# Robot_Arm_2_0.net
KiCad netlist of a schematic drawn in EAGLE
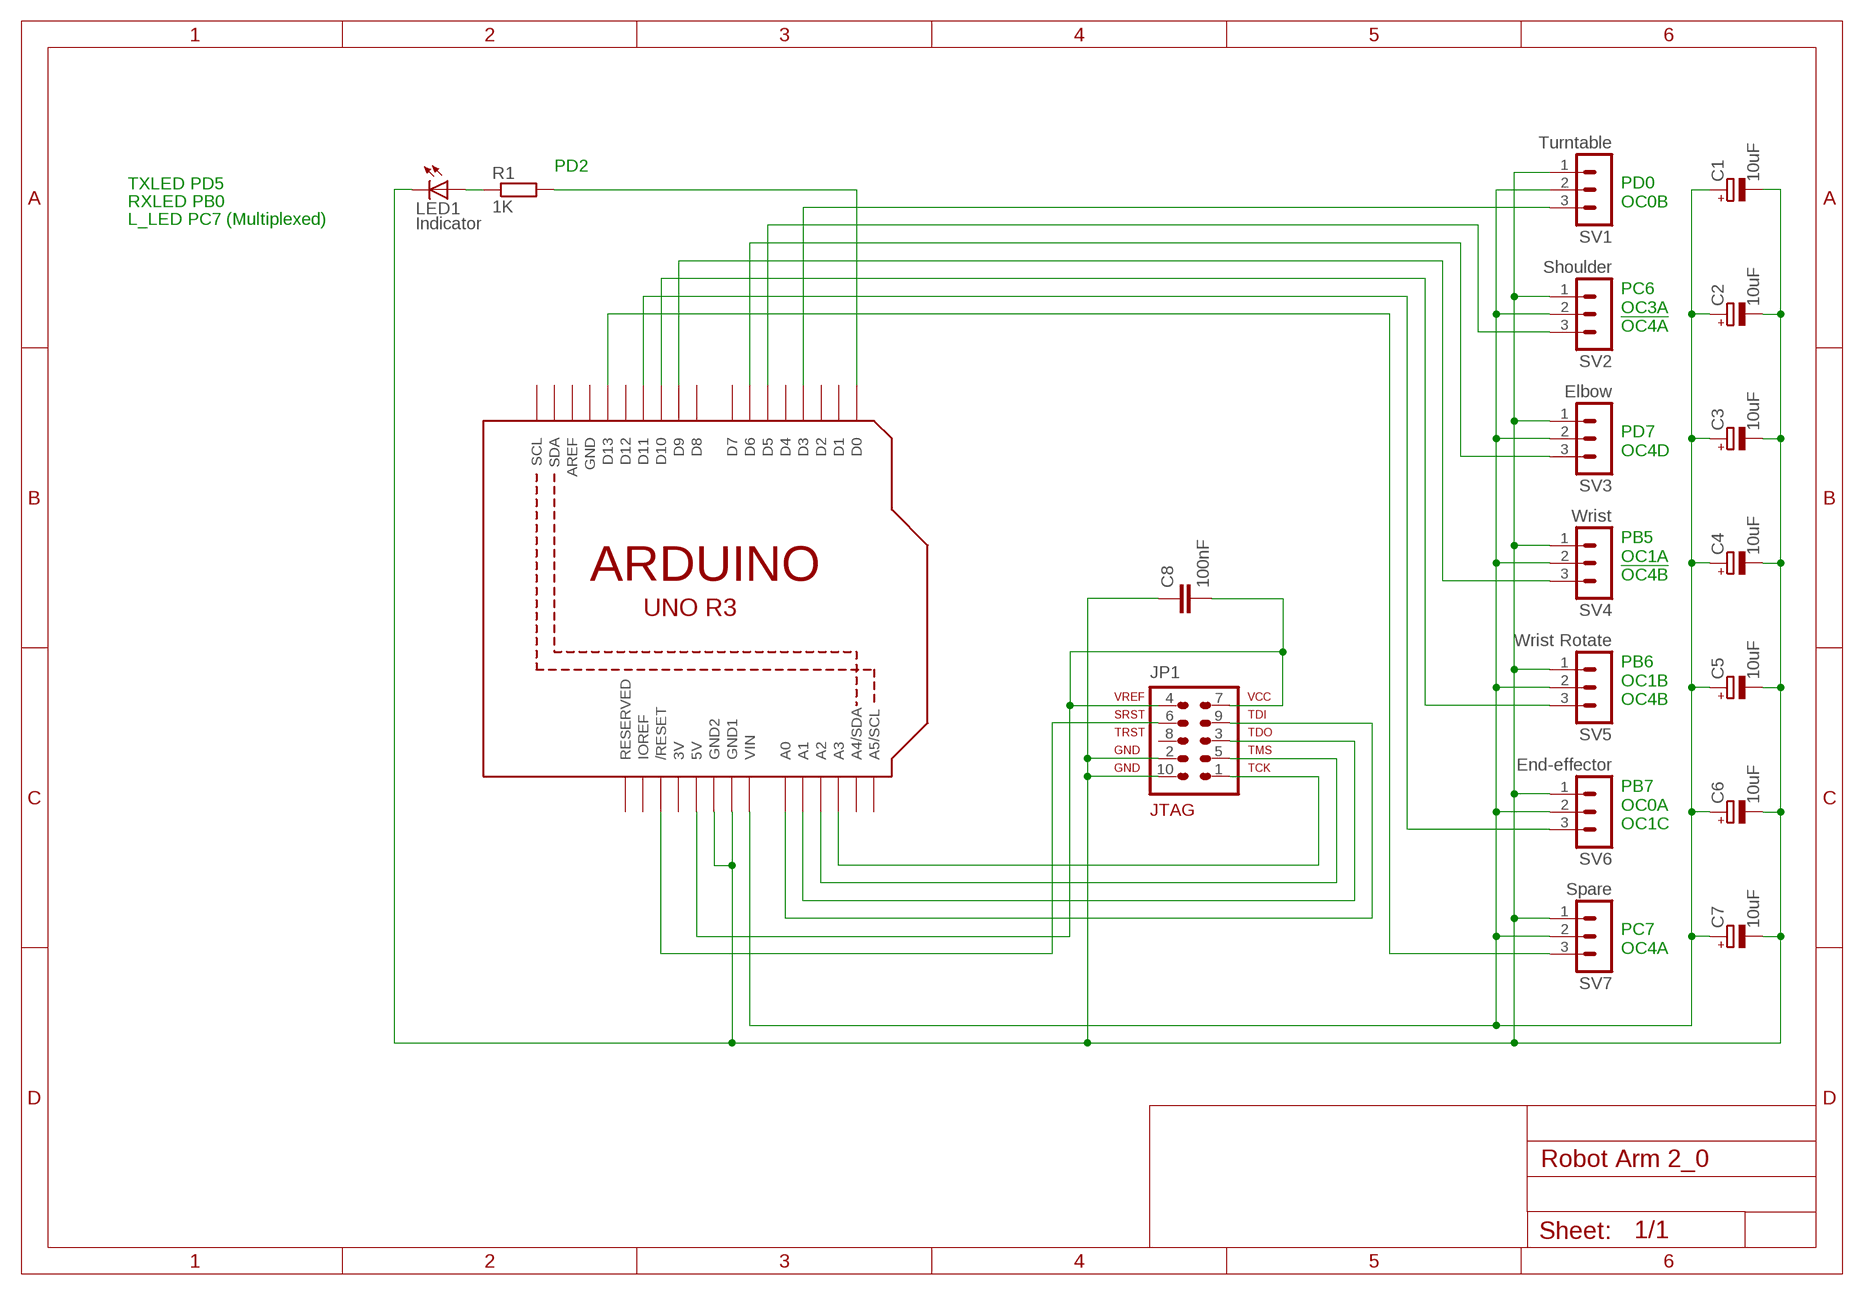
[diagram p0: schematic, sheet 1]

(export (version "E")
  (design (tool "Eeschema 10.0.6"))
  (components
    (comp (ref "C1")
      (value "10uF")
      (footprint "eagle-import:E2,5-5")
      (libsource (lib "eagle-import") (part "CPOL-EUE2.5-5"))
    )
    (comp (ref "C2")
      (value "10uF")
      (footprint "eagle-import:E2,5-5")
      (libsource (lib "eagle-import") (part "CPOL-EUE2.5-5"))
    )
    (comp (ref "C3")
      (value "10uF")
      (footprint "eagle-import:E2,5-5")
      (libsource (lib "eagle-import") (part "CPOL-EUE2.5-5"))
    )
    (comp (ref "C4")
      (value "10uF")
      (footprint "eagle-import:E2,5-5")
      (libsource (lib "eagle-import") (part "CPOL-EUE2.5-5"))
    )
    (comp (ref "C5")
      (value "10uF")
      (footprint "eagle-import:E2,5-5")
      (libsource (lib "eagle-import") (part "CPOL-EUE2.5-5"))
    )
    (comp (ref "C6")
      (value "10uF")
      (footprint "eagle-import:E2,5-5")
      (libsource (lib "eagle-import") (part "CPOL-EUE2.5-5"))
    )
    (comp (ref "C7")
      (value "10uF")
      (footprint "eagle-import:E2,5-5")
      (libsource (lib "eagle-import") (part "CPOL-EUE2.5-5"))
    )
    (comp (ref "C8")
      (value "100nF")
      (footprint "eagle-import:C075-032X103")
      (libsource (lib "eagle-import") (part "C-EU075-032X103"))
    )
    (comp (ref "JP1")
      (value "AVR-JTAG-10")
      (footprint "eagle-import:AVR-JTAG-10")
      (libsource (lib "eagle-import") (part "AVR-JTAG-10"))
    )
    (comp (ref "LED1")
      (value "Indicator")
      (footprint "eagle-import:LED3MM")
      (libsource (lib "eagle-import") (part "LED3MM"))
    )
    (comp (ref "R1")
      (value "1K")
      (footprint "eagle-import:0207_10")
      (libsource (lib "eagle-import") (part "R-EU_0207/10"))
    )
    (comp (ref "SV1")
      (value "Turntable")
      (footprint "eagle-import:MA03-1")
      (libsource (lib "eagle-import") (part "MA03-1"))
    )
    (comp (ref "SV2")
      (value "Shoulder")
      (footprint "eagle-import:MA03-1")
      (libsource (lib "eagle-import") (part "MA03-1"))
    )
    (comp (ref "SV3")
      (value "Elbow")
      (footprint "eagle-import:MA03-1")
      (libsource (lib "eagle-import") (part "MA03-1"))
    )
    (comp (ref "SV4")
      (value "Wrist")
      (footprint "eagle-import:MA03-1")
      (libsource (lib "eagle-import") (part "MA03-1"))
    )
    (comp (ref "SV5")
      (value "Wrist Rotate")
      (footprint "eagle-import:MA03-1")
      (libsource (lib "eagle-import") (part "MA03-1"))
    )
    (comp (ref "SV6")
      (value "End-effector")
      (footprint "eagle-import:MA03-1")
      (libsource (lib "eagle-import") (part "MA03-1"))
    )
    (comp (ref "SV7")
      (value "Spare")
      (footprint "eagle-import:MA03-1")
      (libsource (lib "eagle-import") (part "MA03-1"))
    )
    (comp (ref "U1")
      (value "ARDUINOR3-DIMENSION")
      (footprint "eagle-import:ARDUINOR3")
      (libsource (lib "eagle-import") (part "ARDUINOR3-DIMENSION"))
    )
  )
  (nets
    (net (code "1") (name "/3V") (class "Default")
      (node (ref "U1") (pin "3V") (pinfunction "3V_3V") (pintype "power_in"))
    )
    (net (code "2") (name "/GND") (class "Default")
      (node (ref "U1") (pin "GND") (pinfunction "GND_GND") (pintype "power_in"))
    )
    (net (code "3") (name "Net-(C1-Pad+)") (class "Default")
      (node (ref "C1") (pin "+") (pinfunction "+_+") (pintype "passive"))
      (node (ref "C2") (pin "+") (pinfunction "+_+") (pintype "passive"))
      (node (ref "C3") (pin "+") (pinfunction "+_+") (pintype "passive"))
      (node (ref "C4") (pin "+") (pinfunction "+_+") (pintype "passive"))
      (node (ref "C5") (pin "+") (pinfunction "+_+") (pintype "passive"))
      (node (ref "C6") (pin "+") (pinfunction "+_+") (pintype "passive"))
      (node (ref "C7") (pin "+") (pinfunction "+_+") (pintype "passive"))
      (node (ref "SV1") (pin "2") (pinfunction "2_2") (pintype "passive"))
      (node (ref "SV2") (pin "2") (pinfunction "2_2") (pintype "passive"))
      (node (ref "SV3") (pin "2") (pinfunction "2_2") (pintype "passive"))
      (node (ref "SV4") (pin "2") (pinfunction "2_2") (pintype "passive"))
      (node (ref "SV5") (pin "2") (pinfunction "2_2") (pintype "passive"))
      (node (ref "SV6") (pin "2") (pinfunction "2_2") (pintype "passive"))
      (node (ref "SV7") (pin "2") (pinfunction "2_2") (pintype "passive"))
      (node (ref "U1") (pin "VIN") (pinfunction "VIN_VIN") (pintype "power_in"))
    )
    (net (code "4") (name "Net-(C8-Pad2)") (class "Default")
      (node (ref "C8") (pin "2") (pinfunction "2_2") (pintype "passive"))
      (node (ref "JP1") (pin "4") (pinfunction "4_4") (pintype "passive"))
      (node (ref "JP1") (pin "7") (pinfunction "7_7") (pintype "passive"))
      (node (ref "U1") (pin "5V") (pinfunction "5V_5V") (pintype "power_in"))
    )
    (net (code "5") (name "Net-(JP1-Pad1)") (class "Default")
      (node (ref "JP1") (pin "1") (pinfunction "1_1") (pintype "passive"))
      (node (ref "U1") (pin "A3") (pinfunction "A3_A3") (pintype "bidirectional"))
    )
    (net (code "6") (name "Net-(JP1-Pad3)") (class "Default")
      (node (ref "JP1") (pin "3") (pinfunction "3_3") (pintype "passive"))
      (node (ref "U1") (pin "A1") (pinfunction "A1_A1") (pintype "bidirectional"))
    )
    (net (code "7") (name "Net-(JP1-Pad5)") (class "Default")
      (node (ref "JP1") (pin "5") (pinfunction "5_5") (pintype "passive"))
      (node (ref "U1") (pin "A2") (pinfunction "A2_A2") (pintype "bidirectional"))
    )
    (net (code "8") (name "Net-(JP1-Pad9)") (class "Default")
      (node (ref "JP1") (pin "9") (pinfunction "9_9") (pintype "passive"))
      (node (ref "U1") (pin "A0") (pinfunction "A0_A0") (pintype "bidirectional"))
    )
    (net (code "9") (name "Net-(LED1-C)") (class "Default")
      (node (ref "C1") (pin "-") (pinfunction "-_-") (pintype "passive"))
      (node (ref "C2") (pin "-") (pinfunction "-_-") (pintype "passive"))
      (node (ref "C3") (pin "-") (pinfunction "-_-") (pintype "passive"))
      (node (ref "C4") (pin "-") (pinfunction "-_-") (pintype "passive"))
      (node (ref "C5") (pin "-") (pinfunction "-_-") (pintype "passive"))
      (node (ref "C6") (pin "-") (pinfunction "-_-") (pintype "passive"))
      (node (ref "C7") (pin "-") (pinfunction "-_-") (pintype "passive"))
      (node (ref "C8") (pin "1") (pinfunction "1_1") (pintype "passive"))
      (node (ref "JP1") (pin "10") (pinfunction "10_10") (pintype "passive"))
      (node (ref "JP1") (pin "2") (pinfunction "2_2") (pintype "passive"))
      (node (ref "LED1") (pin "K") (pinfunction "C_K") (pintype "passive"))
      (node (ref "SV1") (pin "1") (pinfunction "1_1") (pintype "passive"))
      (node (ref "SV2") (pin "1") (pinfunction "1_1") (pintype "passive"))
      (node (ref "SV3") (pin "1") (pinfunction "1_1") (pintype "passive"))
      (node (ref "SV4") (pin "1") (pinfunction "1_1") (pintype "passive"))
      (node (ref "SV5") (pin "1") (pinfunction "1_1") (pintype "passive"))
      (node (ref "SV6") (pin "1") (pinfunction "1_1") (pintype "passive"))
      (node (ref "SV7") (pin "1") (pinfunction "1_1") (pintype "passive"))
      (node (ref "U1") (pin "GND1") (pinfunction "GND1_GND1") (pintype "power_in"))
      (node (ref "U1") (pin "GND2") (pinfunction "GND2_GND2") (pintype "power_in"))
    )
    (net (code "10") (name "Net-(LED1-PadA)") (class "Default")
      (node (ref "LED1") (pin "A") (pinfunction "A_A") (pintype "passive"))
      (node (ref "R1") (pin "1") (pinfunction "1_1") (pintype "passive"))
    )
    (net (code "11") (name "Net-(R1-Pad2)") (class "Default")
      (node (ref "R1") (pin "2") (pinfunction "2_2") (pintype "passive"))
      (node (ref "U1") (pin "D0") (pinfunction "D0_D0") (pintype "bidirectional"))
    )
    (net (code "12") (name "Net-(SV1-Pad3)") (class "Default")
      (node (ref "SV1") (pin "3") (pinfunction "3_3") (pintype "passive"))
      (node (ref "U1") (pin "D3") (pinfunction "D3_D3") (pintype "bidirectional"))
    )
    (net (code "13") (name "Net-(SV2-Pad3)") (class "Default")
      (node (ref "SV2") (pin "3") (pinfunction "3_3") (pintype "passive"))
      (node (ref "U1") (pin "D5") (pinfunction "D5_D5") (pintype "bidirectional"))
    )
    (net (code "14") (name "Net-(SV3-Pad3)") (class "Default")
      (node (ref "SV3") (pin "3") (pinfunction "3_3") (pintype "passive"))
      (node (ref "U1") (pin "D6") (pinfunction "D6_D6") (pintype "bidirectional"))
    )
    (net (code "15") (name "Net-(SV4-Pad3)") (class "Default")
      (node (ref "SV4") (pin "3") (pinfunction "3_3") (pintype "passive"))
      (node (ref "U1") (pin "D9") (pinfunction "D9_D9") (pintype "bidirectional"))
    )
    (net (code "16") (name "Net-(SV5-Pad3)") (class "Default")
      (node (ref "SV5") (pin "3") (pinfunction "3_3") (pintype "passive"))
      (node (ref "U1") (pin "D10") (pinfunction "D10_D10") (pintype "bidirectional"))
    )
    (net (code "17") (name "Net-(SV6-Pad3)") (class "Default")
      (node (ref "SV6") (pin "3") (pinfunction "3_3") (pintype "passive"))
      (node (ref "U1") (pin "D11") (pinfunction "D11_D11") (pintype "bidirectional"))
    )
    (net (code "18") (name "Net-(SV7-Pad3)") (class "Default")
      (node (ref "SV7") (pin "3") (pinfunction "3_3") (pintype "passive"))
      (node (ref "U1") (pin "D13") (pinfunction "D13_D13") (pintype "bidirectional"))
    )
    (net (code "19") (name "Net-(U1-{slash}RESET)") (class "Default")
      (node (ref "JP1") (pin "6") (pinfunction "6_6") (pintype "passive"))
      (node (ref "U1") (pin "RESET") (pinfunction "/RESET_RESET") (pintype "bidirectional"))
    )
    (net (code "20") (name "unconnected-(JP1-Pad8)") (class "Default")
      (node (ref "JP1") (pin "8") (pinfunction "8_8") (pintype "passive"))
    )
    (net (code "21") (name "unconnected-(U1-A4{slash}SDA-PadA4)") (class "Default")
      (node (ref "U1") (pin "A4") (pinfunction "A4/SDA_A4") (pintype "bidirectional"))
    )
    (net (code "22") (name "unconnected-(U1-A5{slash}SCL-PadA5)") (class "Default")
      (node (ref "U1") (pin "A5") (pinfunction "A5/SCL_A5") (pintype "bidirectional"))
    )
    (net (code "23") (name "unconnected-(U1-PadAREF)") (class "Default")
      (node (ref "U1") (pin "AREF") (pinfunction "AREF_AREF") (pintype "bidirectional"))
    )
    (net (code "24") (name "unconnected-(U1-PadD1)") (class "Default")
      (node (ref "U1") (pin "D1") (pinfunction "D1_D1") (pintype "bidirectional"))
    )
    (net (code "25") (name "unconnected-(U1-PadD2)") (class "Default")
      (node (ref "U1") (pin "D2") (pinfunction "D2_D2") (pintype "bidirectional"))
    )
    (net (code "26") (name "unconnected-(U1-PadD4)") (class "Default")
      (node (ref "U1") (pin "D4") (pinfunction "D4_D4") (pintype "bidirectional"))
    )
    (net (code "27") (name "unconnected-(U1-PadD7)") (class "Default")
      (node (ref "U1") (pin "D7") (pinfunction "D7_D7") (pintype "bidirectional"))
    )
    (net (code "28") (name "unconnected-(U1-PadD8)") (class "Default")
      (node (ref "U1") (pin "D8") (pinfunction "D8_D8") (pintype "bidirectional"))
    )
    (net (code "29") (name "unconnected-(U1-PadD12)") (class "Default")
      (node (ref "U1") (pin "D12") (pinfunction "D12_D12") (pintype "bidirectional"))
    )
    (net (code "30") (name "unconnected-(U1-PadIOREF)") (class "Default")
      (node (ref "U1") (pin "IOREF") (pinfunction "IOREF_IOREF") (pintype "output"))
    )
    (net (code "31") (name "unconnected-(U1-PadRESERVED)") (class "Default")
      (node (ref "U1") (pin "RESERVED") (pinfunction "RESERVED_RESERVED") (pintype "no_connect"))
    )
    (net (code "32") (name "unconnected-(U1-PadSCL)") (class "Default")
      (node (ref "U1") (pin "SCL") (pinfunction "SCL_SCL") (pintype "bidirectional"))
    )
    (net (code "33") (name "unconnected-(U1-PadSDA)") (class "Default")
      (node (ref "U1") (pin "SDA") (pinfunction "SDA_SDA") (pintype "bidirectional"))
    )
  )
)
